# Sheet1.net
KiCad netlist of a schematic drawn in Altium Designer
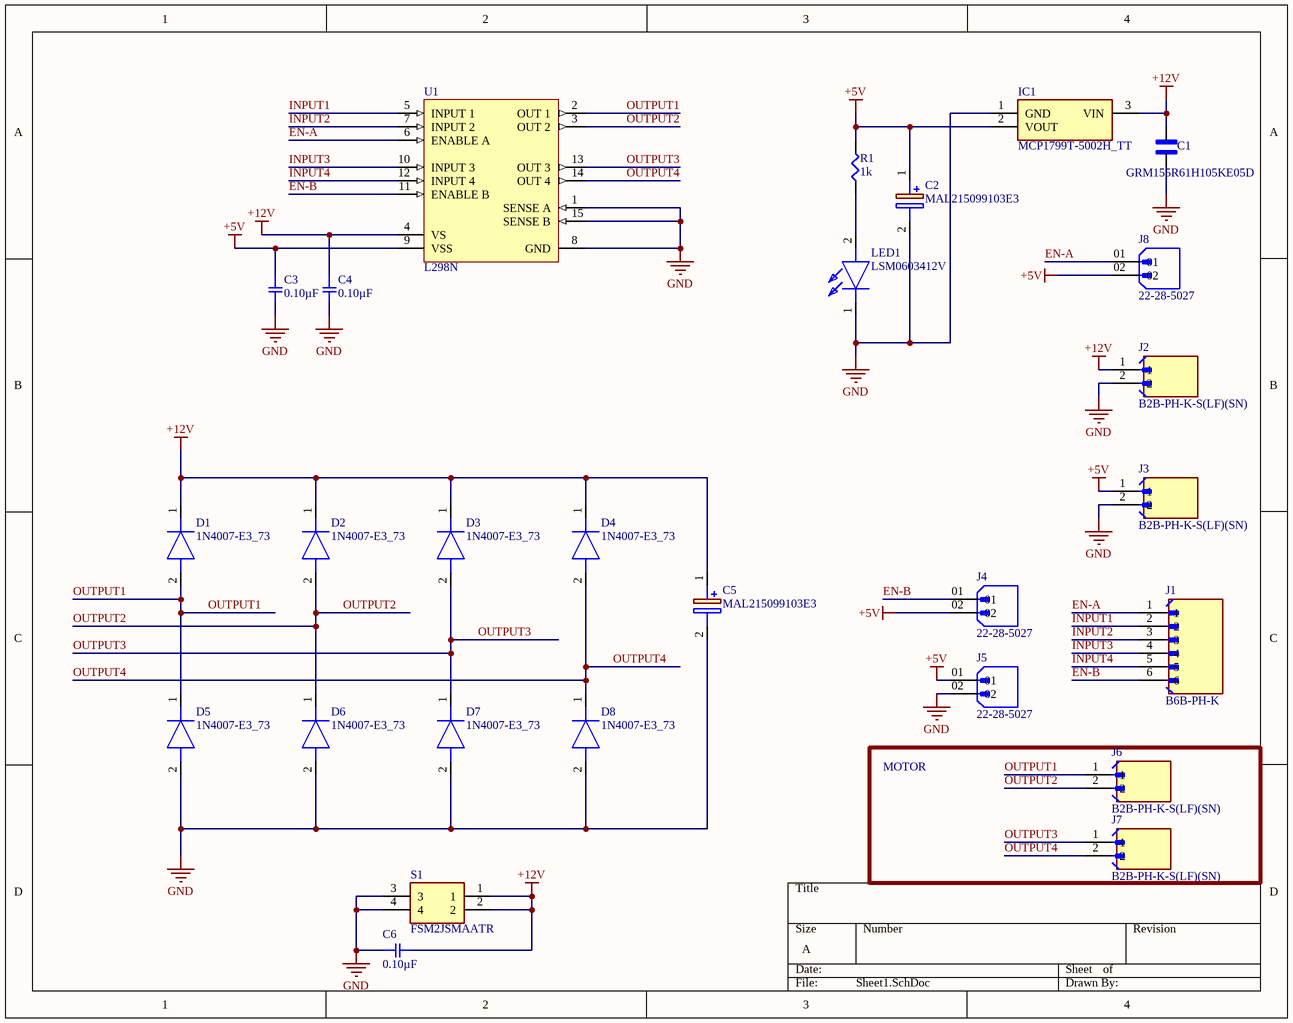
[diagram p0: Sheet1.SchDoc]

(export (version "E")
  (design (tool "Eeschema 10.0.6"))
  (components
    (comp (ref "C1")
      (value "GRM155R61H105KE05D")
      (footprint "GRM155R61H105KE05D:CAPC1005X60N")
      (description "Capacitor Ceramic Multilayer (MLCC)")
      (fields (field (name "MF") "{'manufacturer': u'Murata'}"))
      (libsource (lib "*") (part "GRM155R61H105KE05D"))
    )
    (comp (ref "C2")
      (value "MAL215099103E3")
      (footprint "SamacSys:CAPAE1050X1250N")
      (description "Capacitor Polarised")
      (fields (field (name "MOUSER PART NUMBER") "594-MAL215099103E3"))
      (libsource (lib "*") (part "MAL215099103E3"))
    )
    (comp (ref "C3")
      (value "0.10µF")
      (footprint "SMD-0402C")
      (description "CAP CER 0.1UF 50V X5R 0402")
      (fields
        (field (name "DIGI-KEY PART NUMBER") "490-10697-1-ND")
        (field (name "PART NUMBER") "GRM155R61H104KE14D")
      )
      (libsource (lib "capacitor_murata_0402") (part "GRM155R61H104KE14D"))
    )
    (comp (ref "C4")
      (value "0.10µF")
      (footprint "SMD-0402C")
      (description "CAP CER 0.1UF 50V X5R 0402")
      (fields
        (field (name "DIGI-KEY PART NUMBER") "490-10697-1-ND")
        (field (name "PART NUMBER") "GRM155R61H104KE14D")
      )
      (libsource (lib "capacitor_murata_0402") (part "GRM155R61H104KE14D"))
    )
    (comp (ref "C5")
      (value "MAL215099103E3")
      (footprint "SamacSys:CAPAE1050X1250N")
      (description "Capacitor Polarised")
      (fields (field (name "MOUSER PART NUMBER") "594-MAL215099103E3"))
      (libsource (lib "*") (part "MAL215099103E3"))
    )
    (comp (ref "C6")
      (value "0.10µF")
      (footprint "SMD-0402C")
      (description "CAP CER 0.1UF 50V X5R 0402")
      (fields
        (field (name "DIGI-KEY PART NUMBER") "490-10697-1-ND")
        (field (name "PART NUMBER") "GRM155R61H104KE14D")
      )
      (libsource (lib "capacitor_murata_0402") (part "GRM155R61H104KE14D"))
    )
    (comp (ref "D1")
      (value "1N4007-E3_73")
      (footprint "PCBComponent_1")
      (description "Diode")
      (fields
        (field (name "MANUFACTURER_PART_NUMBER") "1N4007-E3/73")
        (field (name "MOUSER PART NUMBER") "625-1N4007-E3/73")
      )
      (libsource (lib "SamacSys") (part "1N4007-E3_73"))
    )
    (comp (ref "D2")
      (value "1N4007-E3_73")
      (footprint "PCBComponent_1")
      (description "Diode")
      (fields
        (field (name "MANUFACTURER_PART_NUMBER") "1N4007-E3/73")
        (field (name "MOUSER PART NUMBER") "625-1N4007-E3/73")
      )
      (libsource (lib "SamacSys") (part "1N4007-E3_73"))
    )
    (comp (ref "D3")
      (value "1N4007-E3_73")
      (footprint "PCBComponent_1")
      (description "Diode")
      (fields
        (field (name "MANUFACTURER_PART_NUMBER") "1N4007-E3/73")
        (field (name "MOUSER PART NUMBER") "625-1N4007-E3/73")
      )
      (libsource (lib "SamacSys") (part "1N4007-E3_73"))
    )
    (comp (ref "D4")
      (value "1N4007-E3_73")
      (footprint "PCBComponent_1")
      (description "Diode")
      (fields
        (field (name "MANUFACTURER_PART_NUMBER") "1N4007-E3/73")
        (field (name "MOUSER PART NUMBER") "625-1N4007-E3/73")
      )
      (libsource (lib "SamacSys") (part "1N4007-E3_73"))
    )
    (comp (ref "D5")
      (value "1N4007-E3_73")
      (footprint "PCBComponent_1")
      (description "Diode")
      (fields
        (field (name "MANUFACTURER_PART_NUMBER") "1N4007-E3/73")
        (field (name "MOUSER PART NUMBER") "625-1N4007-E3/73")
      )
      (libsource (lib "SamacSys") (part "1N4007-E3_73"))
    )
    (comp (ref "D6")
      (value "1N4007-E3_73")
      (footprint "PCBComponent_1")
      (description "Diode")
      (fields
        (field (name "MANUFACTURER_PART_NUMBER") "1N4007-E3/73")
        (field (name "MOUSER PART NUMBER") "625-1N4007-E3/73")
      )
      (libsource (lib "SamacSys") (part "1N4007-E3_73"))
    )
    (comp (ref "D7")
      (value "1N4007-E3_73")
      (footprint "PCBComponent_1")
      (description "Diode")
      (fields
        (field (name "MANUFACTURER_PART_NUMBER") "1N4007-E3/73")
        (field (name "MOUSER PART NUMBER") "625-1N4007-E3/73")
      )
      (libsource (lib "SamacSys") (part "1N4007-E3_73"))
    )
    (comp (ref "D8")
      (value "1N4007-E3_73")
      (footprint "PCBComponent_1")
      (description "Diode")
      (fields
        (field (name "MANUFACTURER_PART_NUMBER") "1N4007-E3/73")
        (field (name "MOUSER PART NUMBER") "625-1N4007-E3/73")
      )
      (libsource (lib "SamacSys") (part "1N4007-E3_73"))
    )
    (comp (ref "IC1")
      (value "MCP1799T-5002H_TT")
      (footprint "SamacSys:SOT95P237X112-3N")
      (description "Integrated Circuit")
      (fields
        (field (name "MANUFACTURER_PART_NUMBER") "MCP1799T-5002H/TT")
        (field (name "MOUSER PART NUMBER") "579-CP1799T-5002H/TT")
      )
      (libsource (lib "*") (part "MCP1799T-5002H_TT"))
    )
    (comp (ref "J1")
      (value "B6B-PH-K")
      (footprint "B6B-PH-K:JST_B6B-PH-K")
      (fields (field (name "MF") "{'manufacturer': u'JST Corporation'}"))
      (libsource (lib "*") (part "B6B-PH-K"))
    )
    (comp (ref "J2")
      (value "B2B-PH-K-S(LF)(SN)")
      (footprint "B2B-PH-K-S (LF)(SN):JST_B2B-PH-K-S(LF)(SN)")
      (fields (field (name "MF") "{'manufacturer': u'JST'}"))
      (libsource (lib "*") (part "B2B-PH-K-S(LF)(SN)"))
    )
    (comp (ref "J3")
      (value "B2B-PH-K-S(LF)(SN)")
      (footprint "B2B-PH-K-S (LF)(SN):JST_B2B-PH-K-S(LF)(SN)")
      (fields (field (name "MF") "{'manufacturer': u'JST'}"))
      (libsource (lib "*") (part "B2B-PH-K-S(LF)(SN)"))
    )
    (comp (ref "J4")
      (value "22-28-5027")
      (footprint "22-28-5027:MOLEX_22-28-5027")
      (fields (field (name "MF") "{'manufacturer': u'Molex'}"))
      (libsource (lib "*") (part "22-28-5027"))
    )
    (comp (ref "J5")
      (value "22-28-5027")
      (footprint "22-28-5027:MOLEX_22-28-5027")
      (fields (field (name "MF") "{'manufacturer': u'Molex'}"))
      (libsource (lib "*") (part "22-28-5027"))
    )
    (comp (ref "J6")
      (value "B2B-PH-K-S(LF)(SN)")
      (footprint "B2B-PH-K-S (LF)(SN):JST_B2B-PH-K-S(LF)(SN)")
      (fields (field (name "MF") "{'manufacturer': u'JST'}"))
      (libsource (lib "*") (part "B2B-PH-K-S(LF)(SN)"))
    )
    (comp (ref "J7")
      (value "B2B-PH-K-S(LF)(SN)")
      (footprint "B2B-PH-K-S (LF)(SN):JST_B2B-PH-K-S(LF)(SN)")
      (fields (field (name "MF") "{'manufacturer': u'JST'}"))
      (libsource (lib "*") (part "B2B-PH-K-S(LF)(SN)"))
    )
    (comp (ref "J8")
      (value "22-28-5027")
      (footprint "22-28-5027:MOLEX_22-28-5027")
      (fields (field (name "MF") "{'manufacturer': u'Molex'}"))
      (libsource (lib "*") (part "22-28-5027"))
    )
    (comp (ref "LED1")
      (value "LSM0603412V")
      (footprint "SamacSys:LSM0603412V")
      (description "LED")
      (fields (field (name "MOUSER PART NUMBER") "593-LSM0603412V"))
      (libsource (lib "SamacSys") (part "LSM0603412V"))
    )
    (comp (ref "R1")
      (value "1k")
      (footprint "SMD-0402-RES")
      (description "RES SMD 1K OHM 5% 1/10W 0402")
      (fields (field (name "PART NUMBER") "ERJ-2GEJ102X") (field (name "DIGI-KEY PART NUMBER") "P1.0KJCT-ND"))
      (libsource (lib "Panasonic_ERJ_0402") (part "ERJ-2GEJ102X"))
    )
    (comp (ref "S1")
      (value "FSM2JSMAATR")
      (footprint "SamacSys:FSM2J_1")
      (description "Switch")
      (fields (field (name "MOUSER PART NUMBER") "506-FSM2JSMAATR"))
      (libsource (lib "SamacSys") (part "FSM2JSMAATR"))
    )
    (comp (ref "U1")
      (value "L298N")
      (footprint "STM-FM-15")
      (description "Dual Full-Bridge Driver, 4.8 to 46 V, -40 to 150 degC, 15-Pin FM (MW 15L), RoHS, Tube")
      (fields (field (name "MANUFACTURER") "STMicroelectronics") (field (name "PARTNUMBER") "L298"))
      (libsource (lib "Altium Content Vault") (part "STM-L298-15"))
    )
  )
  (nets
    (net (code "1") (name "+5V") (class "Default")
      (node (ref "C2") (pin "1") (pinfunction "+_1") (pintype "passive"))
      (node (ref "C3") (pin "1") (pinfunction "1_1") (pintype "passive"))
      (node (ref "IC1") (pin "2") (pinfunction "VOUT_2") (pintype "passive"))
      (node (ref "J3") (pin "1") (pinfunction "1_1") (pintype "passive"))
      (node (ref "J4") (pin "02") (pinfunction "02_02") (pintype "passive"))
      (node (ref "J5") (pin "01") (pinfunction "01_01") (pintype "passive"))
      (node (ref "J8") (pin "02") (pinfunction "02_02") (pintype "passive"))
      (node (ref "R1") (pin "2") (pinfunction "2_2") (pintype "passive"))
      (node (ref "U1") (pin "9") (pinfunction "VSS_9") (pintype "power_in"))
    )
    (net (code "2") (name "+12V") (class "Default")
      (node (ref "C1") (pin "2") (pinfunction "2_2") (pintype "passive"))
      (node (ref "C4") (pin "1") (pinfunction "1_1") (pintype "passive"))
      (node (ref "C5") (pin "1") (pinfunction "+_1") (pintype "passive"))
      (node (ref "C6") (pin "2") (pinfunction "2_2") (pintype "passive"))
      (node (ref "D1") (pin "1") (pinfunction "K_1") (pintype "passive"))
      (node (ref "D2") (pin "1") (pinfunction "K_1") (pintype "passive"))
      (node (ref "D3") (pin "1") (pinfunction "K_1") (pintype "passive"))
      (node (ref "D4") (pin "1") (pinfunction "K_1") (pintype "passive"))
      (node (ref "IC1") (pin "3") (pinfunction "VIN_3") (pintype "passive"))
      (node (ref "J2") (pin "1") (pinfunction "1_1") (pintype "passive"))
      (node (ref "S1") (pin "1") (pinfunction "1_1") (pintype "passive"))
      (node (ref "S1") (pin "2") (pinfunction "2_2") (pintype "passive"))
      (node (ref "U1") (pin "4") (pinfunction "VS_4") (pintype "power_in"))
    )
    (net (code "3") (name "/EN-A") (class "Default")
      (node (ref "J1") (pin "1") (pinfunction "1_1") (pintype "passive"))
      (node (ref "J8") (pin "01") (pinfunction "01_01") (pintype "passive"))
      (node (ref "U1") (pin "6") (pinfunction "ENABLE_A_6") (pintype "input"))
    )
    (net (code "4") (name "/EN-B") (class "Default")
      (node (ref "J1") (pin "6") (pinfunction "6_6") (pintype "passive"))
      (node (ref "J4") (pin "01") (pinfunction "01_01") (pintype "passive"))
      (node (ref "U1") (pin "11") (pinfunction "ENABLE_B_11") (pintype "input"))
    )
    (net (code "5") (name "/INPUT1") (class "Default")
      (node (ref "J1") (pin "2") (pinfunction "2_2") (pintype "passive"))
      (node (ref "U1") (pin "5") (pinfunction "INPUT_1_5") (pintype "input"))
    )
    (net (code "6") (name "/INPUT2") (class "Default")
      (node (ref "J1") (pin "3") (pinfunction "3_3") (pintype "passive"))
      (node (ref "U1") (pin "7") (pinfunction "INPUT_2_7") (pintype "input"))
    )
    (net (code "7") (name "/INPUT3") (class "Default")
      (node (ref "J1") (pin "4") (pinfunction "4_4") (pintype "passive"))
      (node (ref "U1") (pin "10") (pinfunction "INPUT_3_10") (pintype "input"))
    )
    (net (code "8") (name "/INPUT4") (class "Default")
      (node (ref "J1") (pin "5") (pinfunction "5_5") (pintype "passive"))
      (node (ref "U1") (pin "12") (pinfunction "INPUT_4_12") (pintype "input"))
    )
    (net (code "9") (name "/OUTPUT1") (class "Default")
      (node (ref "D1") (pin "2") (pinfunction "A_2") (pintype "passive"))
      (node (ref "D5") (pin "1") (pinfunction "K_1") (pintype "passive"))
      (node (ref "J6") (pin "1") (pinfunction "1_1") (pintype "passive"))
      (node (ref "U1") (pin "2") (pinfunction "OUT_1_2") (pintype "output"))
    )
    (net (code "10") (name "/OUTPUT2") (class "Default")
      (node (ref "D2") (pin "2") (pinfunction "A_2") (pintype "passive"))
      (node (ref "D6") (pin "1") (pinfunction "K_1") (pintype "passive"))
      (node (ref "J6") (pin "2") (pinfunction "2_2") (pintype "passive"))
      (node (ref "U1") (pin "3") (pinfunction "OUT_2_3") (pintype "output"))
    )
    (net (code "11") (name "/OUTPUT3") (class "Default")
      (node (ref "D3") (pin "2") (pinfunction "A_2") (pintype "passive"))
      (node (ref "D7") (pin "1") (pinfunction "K_1") (pintype "passive"))
      (node (ref "J7") (pin "1") (pinfunction "1_1") (pintype "passive"))
      (node (ref "U1") (pin "13") (pinfunction "OUT_3_13") (pintype "output"))
    )
    (net (code "12") (name "/OUTPUT4") (class "Default")
      (node (ref "D4") (pin "2") (pinfunction "A_2") (pintype "passive"))
      (node (ref "D8") (pin "1") (pinfunction "K_1") (pintype "passive"))
      (node (ref "J7") (pin "2") (pinfunction "2_2") (pintype "passive"))
      (node (ref "U1") (pin "14") (pinfunction "OUT_4_14") (pintype "output"))
    )
    (net (code "13") (name "GND") (class "Default")
      (node (ref "C1") (pin "1") (pinfunction "1_1") (pintype "passive"))
      (node (ref "C2") (pin "2") (pinfunction "-_2") (pintype "passive"))
      (node (ref "C3") (pin "2") (pinfunction "2_2") (pintype "passive"))
      (node (ref "C4") (pin "2") (pinfunction "2_2") (pintype "passive"))
      (node (ref "C5") (pin "2") (pinfunction "-_2") (pintype "passive"))
      (node (ref "C6") (pin "1") (pinfunction "1_1") (pintype "passive"))
      (node (ref "D5") (pin "2") (pinfunction "A_2") (pintype "passive"))
      (node (ref "D6") (pin "2") (pinfunction "A_2") (pintype "passive"))
      (node (ref "D7") (pin "2") (pinfunction "A_2") (pintype "passive"))
      (node (ref "D8") (pin "2") (pinfunction "A_2") (pintype "passive"))
      (node (ref "IC1") (pin "1") (pinfunction "GND_1") (pintype "passive"))
      (node (ref "J2") (pin "2") (pinfunction "2_2") (pintype "passive"))
      (node (ref "J3") (pin "2") (pinfunction "2_2") (pintype "passive"))
      (node (ref "J5") (pin "02") (pinfunction "02_02") (pintype "passive"))
      (node (ref "LED1") (pin "1") (pinfunction "K_1") (pintype "passive"))
      (node (ref "S1") (pin "3") (pinfunction "3_3") (pintype "passive"))
      (node (ref "S1") (pin "4") (pinfunction "4_4") (pintype "passive"))
      (node (ref "U1") (pin "1") (pinfunction "SENSE_A_1") (pintype "input"))
      (node (ref "U1") (pin "15") (pinfunction "SENSE_B_15") (pintype "input"))
      (node (ref "U1") (pin "8") (pinfunction "GND_8") (pintype "power_in"))
    )
    (net (code "14") (name "Net-(LED1-A)") (class "Default")
      (node (ref "LED1") (pin "2") (pinfunction "A_2") (pintype "passive"))
      (node (ref "R1") (pin "1") (pinfunction "1_1") (pintype "passive"))
    )
  )
)
